# key.net
KiCad netlist of a schematic drawn in EAGLE
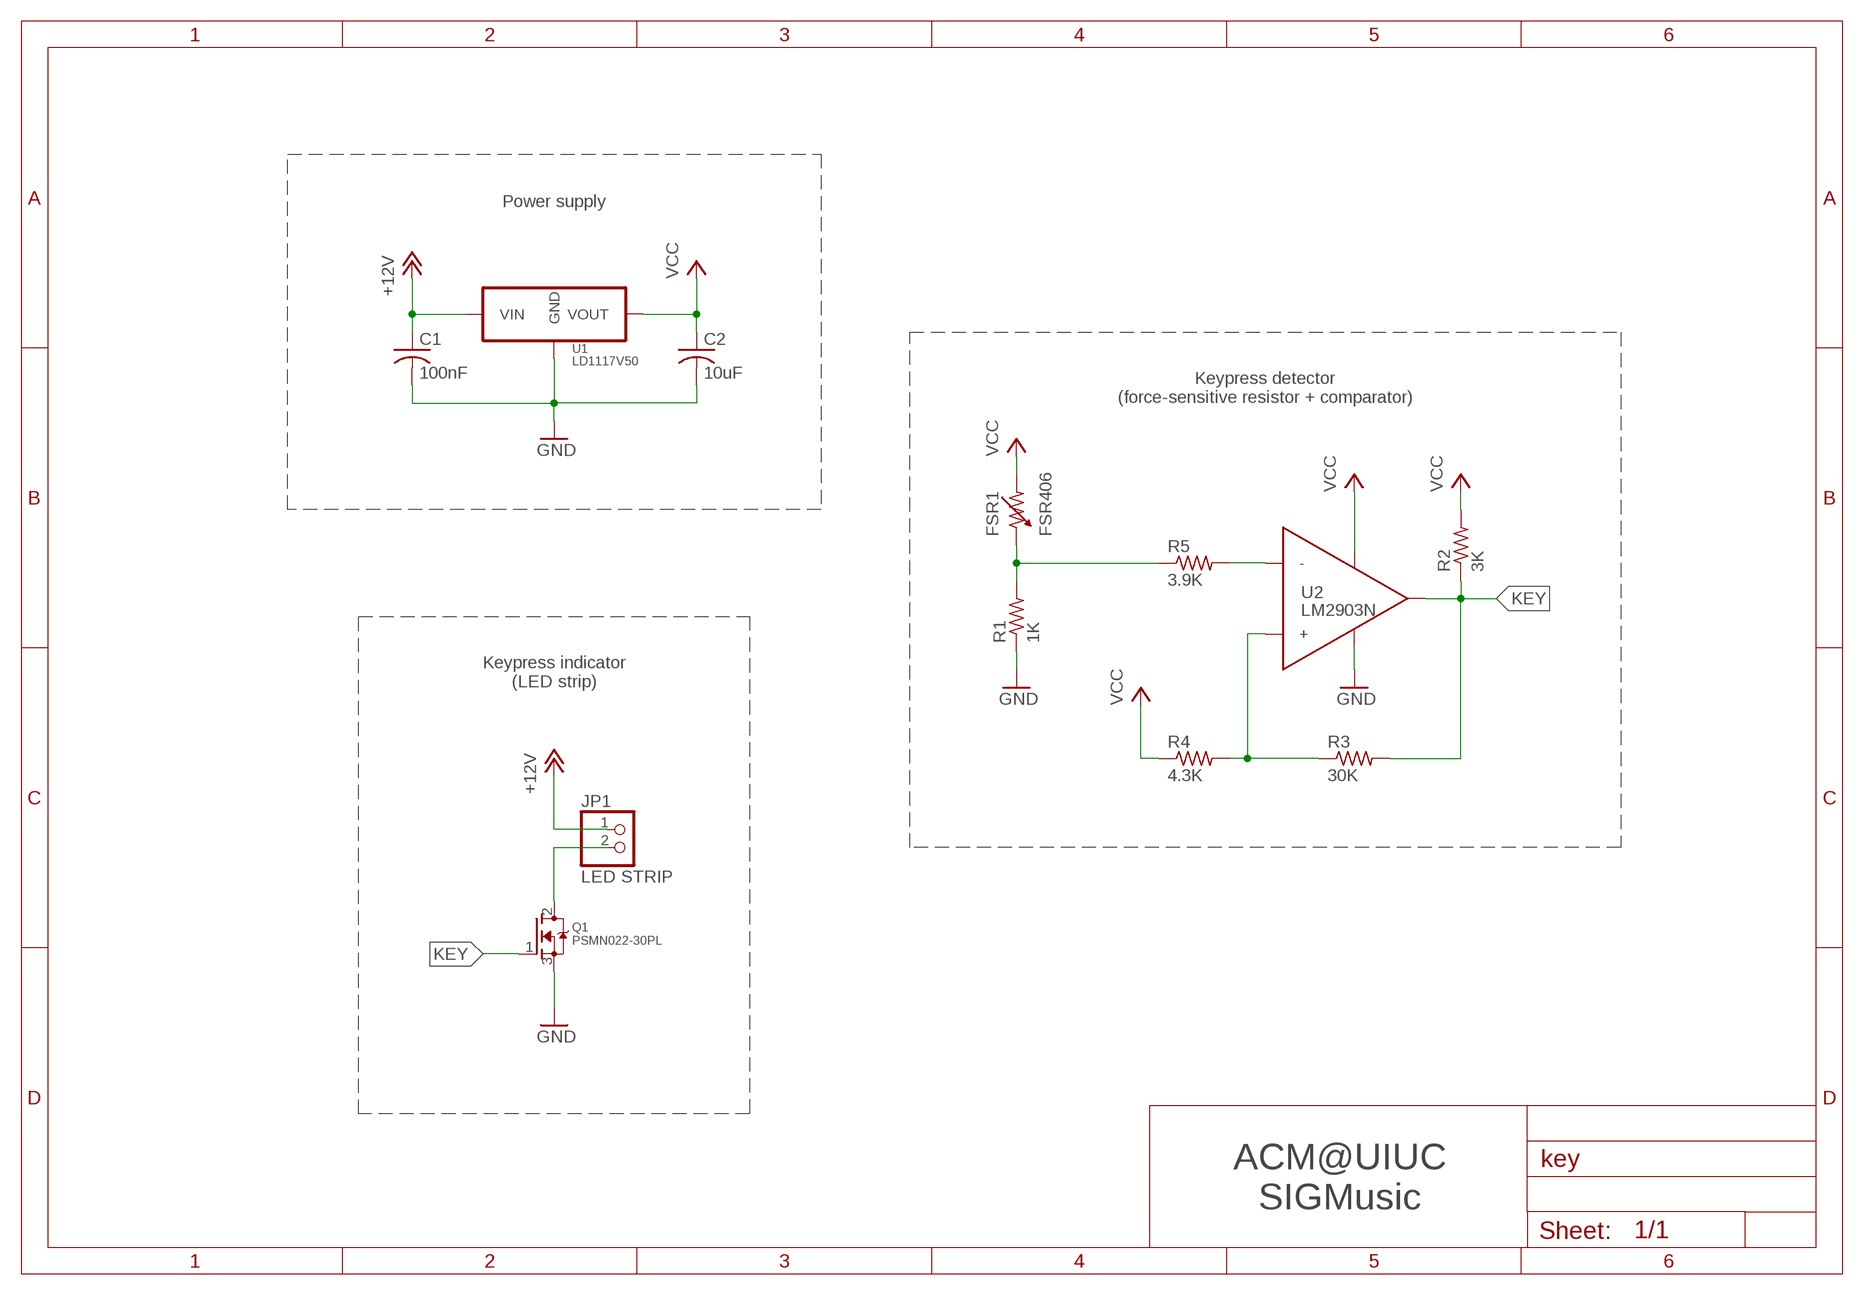
[diagram p0: schematic, sheet 1]

(export (version "E")
  (design (tool "Eeschema 10.0.6"))
  (components
    (comp (ref "C1")
      (value "100nF")
      (footprint "eagle-import:C025-025X050")
      (libsource (lib "eagle-import") (part "C-US025-025X050"))
    )
    (comp (ref "C2")
      (value "10uF")
      (footprint "eagle-import:C025-025X050")
      (libsource (lib "eagle-import") (part "C-US025-025X050"))
    )
    (comp (ref "FSR1")
      (value "FSR406")
      (footprint "eagle-import:FSR-SQUARE")
      (libsource (lib "eagle-import") (part "FSR-SQUARE"))
    )
    (comp (ref "JP1")
      (value "LED STRIP")
      (footprint "eagle-import:1X02_90")
      (libsource (lib "eagle-import") (part "PINHD-1X2/90"))
    )
    (comp (ref "Q1")
      (value "PSMN022-30PL")
      (footprint "eagle-import:TO220V")
      (libsource (lib "eagle-import") (part "MOSFET-NGDS_TO220V"))
    )
    (comp (ref "R1")
      (value "1K")
      (footprint "eagle-import:0207_10")
      (libsource (lib "eagle-import") (part "R-US_0207/10"))
    )
    (comp (ref "R2")
      (value "3K")
      (footprint "eagle-import:0207_10")
      (libsource (lib "eagle-import") (part "R-US_0207/10"))
    )
    (comp (ref "R3")
      (value "30K")
      (footprint "eagle-import:0207_10")
      (libsource (lib "eagle-import") (part "R-US_0207/10"))
    )
    (comp (ref "R4")
      (value "4.3K")
      (footprint "eagle-import:0207_10")
      (libsource (lib "eagle-import") (part "R-US_0207/10"))
    )
    (comp (ref "R5")
      (value "3.9K")
      (footprint "eagle-import:0207_10")
      (libsource (lib "eagle-import") (part "R-US_0207/10"))
    )
    (comp (ref "U1")
      (value "LD1117V50")
      (footprint "eagle-import:TO-220")
      (libsource (lib "eagle-import") (part "LD1117"))
    )
    (comp (ref "U2")
      (value "LM2903N")
      (footprint "eagle-import:DIL08")
      (libsource (lib "eagle-import") (part "LM2903P"))
    )
  )
  (nets
    (net (code "1") (name "+12V") (class "Default")
      (node (ref "C1") (pin "1") (pinfunction "1_1") (pintype "passive"))
      (node (ref "JP1") (pin "1") (pinfunction "1_1") (pintype "passive"))
      (node (ref "U1") (pin "P$3") (pinfunction "VIN_P$3") (pintype "input"))
    )
    (net (code "2") (name "GND") (class "Default")
      (node (ref "C1") (pin "2") (pinfunction "2_2") (pintype "passive"))
      (node (ref "C2") (pin "2") (pinfunction "2_2") (pintype "passive"))
      (node (ref "Q1") (pin "3") (pinfunction "S_3") (pintype "bidirectional"))
      (node (ref "R1") (pin "1") (pinfunction "1_1") (pintype "passive"))
      (node (ref "U1") (pin "P$1") (pinfunction "GND_P$1") (pintype "power_in"))
      (node (ref "U2") (pin "4") (pinfunction "GND_4") (pintype "power_in"))
      (node (ref "U2") (pin "5") (pinfunction "GND_5") (pintype "power_in"))
      (node (ref "U2") (pin "6") (pinfunction "GND_6") (pintype "power_in"))
      (node (ref "U2") (pin "7") (pinfunction "GND_7") (pintype "power_in"))
    )
    (net (code "3") (name "KEY") (class "Default")
      (node (ref "Q1") (pin "1") (pinfunction "G_1") (pintype "bidirectional"))
      (node (ref "R2") (pin "1") (pinfunction "1_1") (pintype "passive"))
      (node (ref "R3") (pin "2") (pinfunction "2_2") (pintype "passive"))
      (node (ref "U2") (pin "1") (pinfunction "P$1_1") (pintype "output"))
    )
    (net (code "4") (name "Net-(FSR1-1)") (class "Default")
      (node (ref "FSR1") (pin "P$1") (pinfunction "1_P$1") (pintype "passive"))
      (node (ref "R1") (pin "2") (pinfunction "2_2") (pintype "passive"))
      (node (ref "R5") (pin "1") (pinfunction "1_1") (pintype "passive"))
    )
    (net (code "5") (name "Net-(Q1-D)") (class "Default")
      (node (ref "JP1") (pin "2") (pinfunction "2_2") (pintype "passive"))
      (node (ref "Q1") (pin "2") (pinfunction "D_2") (pintype "bidirectional"))
    )
    (net (code "6") (name "Net-(U2-+)") (class "Default")
      (node (ref "R3") (pin "1") (pinfunction "1_1") (pintype "passive"))
      (node (ref "R4") (pin "2") (pinfunction "2_2") (pintype "passive"))
      (node (ref "U2") (pin "3") (pinfunction "+_3") (pintype "input"))
    )
    (net (code "7") (name "Net-(U2--)") (class "Default")
      (node (ref "R5") (pin "2") (pinfunction "2_2") (pintype "passive"))
      (node (ref "U2") (pin "2") (pinfunction "-_2") (pintype "input"))
    )
    (net (code "8") (name "VCC") (class "Default")
      (node (ref "C2") (pin "1") (pinfunction "1_1") (pintype "passive"))
      (node (ref "FSR1") (pin "P$2") (pinfunction "2_P$2") (pintype "passive"))
      (node (ref "R2") (pin "2") (pinfunction "2_2") (pintype "passive"))
      (node (ref "R4") (pin "1") (pinfunction "1_1") (pintype "passive"))
      (node (ref "U1") (pin "P$2") (pinfunction "VOUT_P$2") (pintype "output"))
      (node (ref "U1") (pin "P$4") (pinfunction "VOUT_P$4") (pintype "output"))
      (node (ref "U2") (pin "8") (pinfunction "VCC_8") (pintype "power_in"))
    )
  )
)
